# RedBot.net
KiCad netlist of a schematic drawn in EAGLE
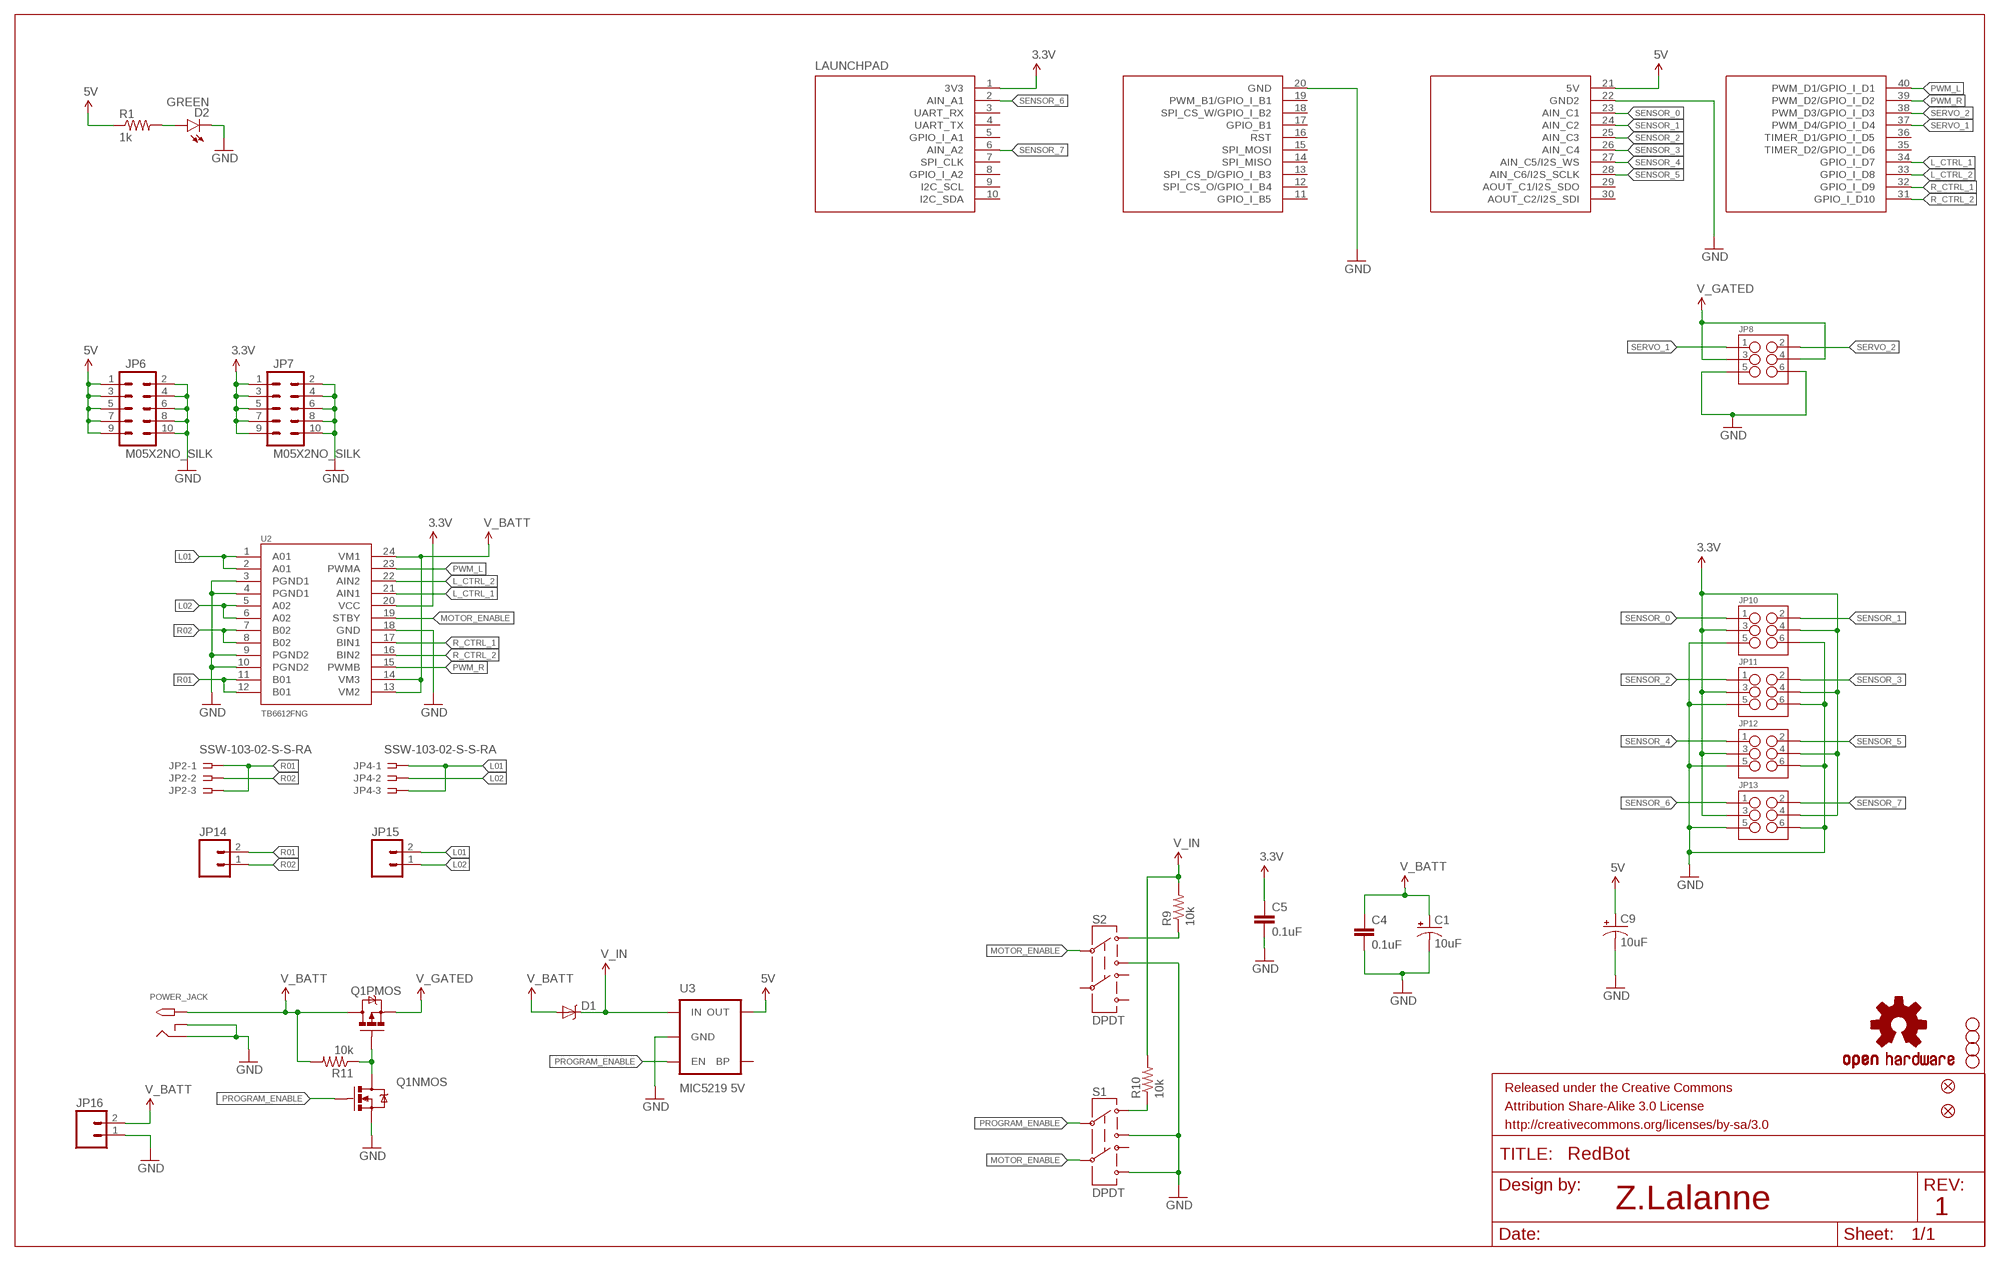
[diagram p0: schematic, sheet 1]

(export (version "E")
  (design (tool "Eeschema 10.0.6"))
  (components
    (comp (ref "C1")
      (value "10uF")
      (footprint "eagle-import:EIA3216")
      (libsource (lib "eagle-import") (part "10UF-16V-10%(TANT)"))
    )
    (comp (ref "C4")
      (value "0.1uF")
      (footprint "eagle-import:1206")
      (libsource (lib "eagle-import") (part "CAP1206"))
    )
    (comp (ref "C5")
      (value "0.1uF")
      (footprint "eagle-import:1206")
      (libsource (lib "eagle-import") (part "CAP1206"))
    )
    (comp (ref "C9")
      (value "10uF")
      (footprint "eagle-import:EIA3216")
      (libsource (lib "eagle-import") (part "10UF-16V-10%(TANT)"))
    )
    (comp (ref "D1")
      (value "B340A")
      (footprint "eagle-import:SMA-DIODE")
      (libsource (lib "eagle-import") (part "B340A"))
    )
    (comp (ref "D2")
      (value "GREEN")
      (footprint "eagle-import:LED-1206")
      (libsource (lib "eagle-import") (part "LED-GREENLARGE"))
    )
    (comp (ref "FID1")
      (value "FIDUCIALUFIDUCIAL")
      (footprint "eagle-import:MICRO-FIDUCIAL")
      (libsource (lib "eagle-import") (part "FIDUCIALUFIDUCIAL"))
    )
    (comp (ref "FID2")
      (value "FIDUCIALUFIDUCIAL")
      (footprint "eagle-import:MICRO-FIDUCIAL")
      (libsource (lib "eagle-import") (part "FIDUCIALUFIDUCIAL"))
    )
    (comp (ref "FRAME1")
      (value "FRAME-LETTER")
      (footprint "eagle-import:CREATIVE_COMMONS")
      (libsource (lib "eagle-import") (part "FRAME-LETTER"))
    )
    (comp (ref "JP2")
      (value "SSW-103-02-S-S-RA")
      (footprint "eagle-import:SSW-103-02-S-S-RA")
      (libsource (lib "eagle-import") (part "SSW-103-02-S-S-RA"))
    )
    (comp (ref "JP4")
      (value "SSW-103-02-S-S-RA")
      (footprint "eagle-import:SSW-103-02-S-S-RA")
      (libsource (lib "eagle-import") (part "SSW-103-02-S-S-RA"))
    )
    (comp (ref "JP6")
      (value "M05X2NO_SILK")
      (footprint "eagle-import:2X5_NOSILK")
      (libsource (lib "eagle-import") (part "M05X2NO_SILK"))
    )
    (comp (ref "JP7")
      (value "M05X2NO_SILK")
      (footprint "eagle-import:2X5_NOSILK")
      (libsource (lib "eagle-import") (part "M05X2NO_SILK"))
    )
    (comp (ref "JP8")
      (value "M03X22X3_SILK_SM")
      (footprint "eagle-import:2X3")
      (libsource (lib "eagle-import") (part "M03X22X3_SILK_SM"))
    )
    (comp (ref "JP10")
      (value "M03X22X3_SILK_SM")
      (footprint "eagle-import:2X3")
      (libsource (lib "eagle-import") (part "M03X22X3_SILK_SM"))
    )
    (comp (ref "JP11")
      (value "M03X22X3_SILK_SM")
      (footprint "eagle-import:2X3")
      (libsource (lib "eagle-import") (part "M03X22X3_SILK_SM"))
    )
    (comp (ref "JP12")
      (value "M03X22X3_SILK_SM")
      (footprint "eagle-import:2X3")
      (libsource (lib "eagle-import") (part "M03X22X3_SILK_SM"))
    )
    (comp (ref "JP13")
      (value "M03X22X3_SILK_SM")
      (footprint "eagle-import:2X3")
      (libsource (lib "eagle-import") (part "M03X22X3_SILK_SM"))
    )
    (comp (ref "JP14")
      (value "M02PTH")
      (footprint "eagle-import:1X02")
      (libsource (lib "eagle-import") (part "M02PTH"))
    )
    (comp (ref "JP15")
      (value "M02PTH")
      (footprint "eagle-import:1X02")
      (libsource (lib "eagle-import") (part "M02PTH"))
    )
    (comp (ref "JP16")
      (value "M02PTH")
      (footprint "eagle-import:1X02")
      (libsource (lib "eagle-import") (part "M02PTH"))
    )
    (comp (ref "LAUNCHPAD")
      (value "BOOSTERPACK")
      (footprint "eagle-import:BOOSTERPACK40")
      (libsource (lib "eagle-import") (part "BOOSTERPACK"))
    )
    (comp (ref "POWER_JACK")
      (value "2.1MMJACKTHM")
      (footprint "eagle-import:PJ-102A")
      (libsource (lib "eagle-import") (part "2.1MMJACKTHM"))
    )
    (comp (ref "Q1")
      (value "IRF7509")
      (footprint "eagle-import:MSOP8")
      (libsource (lib "eagle-import") (part "IRF7509"))
    )
    (comp (ref "R1")
      (value "1k")
      (footprint "eagle-import:1206")
      (libsource (lib "eagle-import") (part "RESISTOR1206"))
    )
    (comp (ref "R9")
      (value "10k")
      (footprint "eagle-import:1206")
      (libsource (lib "eagle-import") (part "RESISTOR1206"))
    )
    (comp (ref "R10")
      (value "10k")
      (footprint "eagle-import:1206")
      (libsource (lib "eagle-import") (part "RESISTOR1206"))
    )
    (comp (ref "R11")
      (value "10k")
      (footprint "eagle-import:1206")
      (libsource (lib "eagle-import") (part "RESISTOR1206"))
    )
    (comp (ref "S1")
      (value "DPDT")
      (footprint "eagle-import:AYZ0202")
      (libsource (lib "eagle-import") (part "SWITCH-DPDTAYZ0202"))
    )
    (comp (ref "S2")
      (value "DPDT")
      (footprint "eagle-import:AYZ0202")
      (libsource (lib "eagle-import") (part "SWITCH-DPDTAYZ0202"))
    )
    (comp (ref "STANDOFF1")
      (value "STAND-OFF")
      (footprint "eagle-import:STAND-OFF")
      (libsource (lib "eagle-import") (part "STAND-OFF"))
    )
    (comp (ref "STANDOFF2")
      (value "STAND-OFF")
      (footprint "eagle-import:STAND-OFF")
      (libsource (lib "eagle-import") (part "STAND-OFF"))
    )
    (comp (ref "STANDOFF3")
      (value "STAND-OFF")
      (footprint "eagle-import:STAND-OFF")
      (libsource (lib "eagle-import") (part "STAND-OFF"))
    )
    (comp (ref "STANDOFF4")
      (value "STAND-OFF")
      (footprint "eagle-import:STAND-OFF")
      (libsource (lib "eagle-import") (part "STAND-OFF"))
    )
    (comp (ref "U$17")
      (value "OSHW-LOGOS")
      (footprint "eagle-import:OSHW-LOGO-S")
      (libsource (lib "eagle-import") (part "OSHW-LOGOS"))
    )
    (comp (ref "U2")
      (value "TB6612FNG")
      (footprint "eagle-import:SSOP24")
      (libsource (lib "eagle-import") (part "TB6621FNG"))
    )
    (comp (ref "U3")
      (value "MIC5219 5V")
      (footprint "eagle-import:SOT23-5")
      (fields (field (name "PROD_ID") "VREG-10107"))
      (libsource (lib "eagle-import") (part "V_REG_MIC52195V"))
    )
  )
  (nets
    (net (code "1") (name "3.3V") (class "Default")
      (node (ref "C5") (pin "1") (pinfunction "1_1") (pintype "passive"))
      (node (ref "JP10") (pin "3") (pinfunction "3_3") (pintype "bidirectional"))
      (node (ref "JP10") (pin "4") (pinfunction "4_4") (pintype "bidirectional"))
      (node (ref "JP11") (pin "3") (pinfunction "3_3") (pintype "bidirectional"))
      (node (ref "JP11") (pin "4") (pinfunction "4_4") (pintype "bidirectional"))
      (node (ref "JP12") (pin "3") (pinfunction "3_3") (pintype "bidirectional"))
      (node (ref "JP12") (pin "4") (pinfunction "4_4") (pintype "bidirectional"))
      (node (ref "JP13") (pin "3") (pinfunction "3_3") (pintype "bidirectional"))
      (node (ref "JP13") (pin "4") (pinfunction "4_4") (pintype "bidirectional"))
      (node (ref "JP7") (pin "1") (pinfunction "1_1") (pintype "passive"))
      (node (ref "JP7") (pin "3") (pinfunction "3_3") (pintype "passive"))
      (node (ref "JP7") (pin "5") (pinfunction "5_5") (pintype "passive"))
      (node (ref "JP7") (pin "7") (pinfunction "7_7") (pintype "passive"))
      (node (ref "JP7") (pin "9") (pinfunction "9_9") (pintype "passive"))
      (node (ref "LAUNCHPAD") (pin "1") (pinfunction "3V3_1") (pintype "power_in"))
      (node (ref "U2") (pin "20") (pinfunction "VCC_20") (pintype "bidirectional"))
    )
    (net (code "2") (name "5V") (class "Default")
      (node (ref "C9") (pin "A") (pinfunction "+_A") (pintype "passive"))
      (node (ref "JP6") (pin "1") (pinfunction "1_1") (pintype "passive"))
      (node (ref "JP6") (pin "3") (pinfunction "3_3") (pintype "passive"))
      (node (ref "JP6") (pin "5") (pinfunction "5_5") (pintype "passive"))
      (node (ref "JP6") (pin "7") (pinfunction "7_7") (pintype "passive"))
      (node (ref "JP6") (pin "9") (pinfunction "9_9") (pintype "passive"))
      (node (ref "LAUNCHPAD") (pin "21") (pinfunction "5V_21") (pintype "power_in"))
      (node (ref "R1") (pin "1") (pinfunction "1_1") (pintype "passive"))
      (node (ref "U3") (pin "5") (pinfunction "OUT_5") (pintype "passive"))
    )
    (net (code "3") (name "GND") (class "Default")
      (node (ref "C1") (pin "C") (pinfunction "-_C") (pintype "passive"))
      (node (ref "C4") (pin "2") (pinfunction "2_2") (pintype "passive"))
      (node (ref "C5") (pin "2") (pinfunction "2_2") (pintype "passive"))
      (node (ref "C9") (pin "C") (pinfunction "-_C") (pintype "passive"))
      (node (ref "D2") (pin "C") (pinfunction "C_C") (pintype "passive"))
      (node (ref "JP10") (pin "5") (pinfunction "5_5") (pintype "bidirectional"))
      (node (ref "JP10") (pin "6") (pinfunction "6_6") (pintype "bidirectional"))
      (node (ref "JP11") (pin "5") (pinfunction "5_5") (pintype "bidirectional"))
      (node (ref "JP11") (pin "6") (pinfunction "6_6") (pintype "bidirectional"))
      (node (ref "JP12") (pin "5") (pinfunction "5_5") (pintype "bidirectional"))
      (node (ref "JP12") (pin "6") (pinfunction "6_6") (pintype "bidirectional"))
      (node (ref "JP13") (pin "5") (pinfunction "5_5") (pintype "bidirectional"))
      (node (ref "JP13") (pin "6") (pinfunction "6_6") (pintype "bidirectional"))
      (node (ref "JP16") (pin "1") (pinfunction "1_1") (pintype "passive"))
      (node (ref "JP6") (pin "10") (pinfunction "10_10") (pintype "passive"))
      (node (ref "JP6") (pin "2") (pinfunction "2_2") (pintype "passive"))
      (node (ref "JP6") (pin "4") (pinfunction "4_4") (pintype "passive"))
      (node (ref "JP6") (pin "6") (pinfunction "6_6") (pintype "passive"))
      (node (ref "JP6") (pin "8") (pinfunction "8_8") (pintype "passive"))
      (node (ref "JP7") (pin "10") (pinfunction "10_10") (pintype "passive"))
      (node (ref "JP7") (pin "2") (pinfunction "2_2") (pintype "passive"))
      (node (ref "JP7") (pin "4") (pinfunction "4_4") (pintype "passive"))
      (node (ref "JP7") (pin "6") (pinfunction "6_6") (pintype "passive"))
      (node (ref "JP7") (pin "8") (pinfunction "8_8") (pintype "passive"))
      (node (ref "JP8") (pin "5") (pinfunction "5_5") (pintype "bidirectional"))
      (node (ref "JP8") (pin "6") (pinfunction "6_6") (pintype "bidirectional"))
      (node (ref "LAUNCHPAD") (pin "20") (pinfunction "GND_20") (pintype "power_in"))
      (node (ref "LAUNCHPAD") (pin "22") (pinfunction "GND2_22") (pintype "power_in"))
      (node (ref "POWER_JACK") (pin "RING") (pinfunction "RING_RING") (pintype "bidirectional"))
      (node (ref "POWER_JACK") (pin "RING_SW") (pinfunction "RING_SW_RING_SW") (pintype "bidirectional"))
      (node (ref "Q1") (pin "1") (pinfunction "S_1") (pintype "passive"))
      (node (ref "S1") (pin "3") (pinfunction "3_3") (pintype "bidirectional"))
      (node (ref "S1") (pin "6") (pinfunction "6_6") (pintype "bidirectional"))
      (node (ref "S2") (pin "3") (pinfunction "3_3") (pintype "bidirectional"))
      (node (ref "U2") (pin "10") (pinfunction "PGND2_10") (pintype "bidirectional"))
      (node (ref "U2") (pin "18") (pinfunction "GND_18") (pintype "bidirectional"))
      (node (ref "U2") (pin "3") (pinfunction "PGND1_3") (pintype "bidirectional"))
      (node (ref "U2") (pin "4") (pinfunction "PGND1_4") (pintype "bidirectional"))
      (node (ref "U2") (pin "9") (pinfunction "PGND2_9") (pintype "bidirectional"))
      (node (ref "U3") (pin "2") (pinfunction "GND_2") (pintype "input"))
    )
    (net (code "4") (name "L01") (class "Default")
      (node (ref "JP15") (pin "2") (pinfunction "2_2") (pintype "passive"))
      (node (ref "JP4") (pin "1") (pinfunction "1_1") (pintype "passive"))
      (node (ref "JP4") (pin "3") (pinfunction "1_3") (pintype "passive"))
      (node (ref "U2") (pin "1") (pinfunction "A01_1") (pintype "bidirectional"))
      (node (ref "U2") (pin "2") (pinfunction "A01_2") (pintype "bidirectional"))
    )
    (net (code "5") (name "L02") (class "Default")
      (node (ref "JP15") (pin "1") (pinfunction "1_1") (pintype "passive"))
      (node (ref "JP4") (pin "2") (pinfunction "1_2") (pintype "passive"))
      (node (ref "U2") (pin "5") (pinfunction "A02_5") (pintype "bidirectional"))
      (node (ref "U2") (pin "6") (pinfunction "A02_6") (pintype "bidirectional"))
    )
    (net (code "6") (name "L_CTRL_1") (class "Default")
      (node (ref "LAUNCHPAD") (pin "34") (pinfunction "GPIO_I_D7_34") (pintype "bidirectional"))
      (node (ref "U2") (pin "21") (pinfunction "AIN1_21") (pintype "bidirectional"))
    )
    (net (code "7") (name "L_CTRL_2") (class "Default")
      (node (ref "LAUNCHPAD") (pin "33") (pinfunction "GPIO_I_D8_33") (pintype "bidirectional"))
      (node (ref "U2") (pin "22") (pinfunction "AIN2_22") (pintype "bidirectional"))
    )
    (net (code "8") (name "MOTOR_ENABLE") (class "Default")
      (node (ref "S1") (pin "5") (pinfunction "5_5") (pintype "bidirectional"))
      (node (ref "S2") (pin "2") (pinfunction "2_2") (pintype "bidirectional"))
      (node (ref "U2") (pin "19") (pinfunction "STBY_19") (pintype "bidirectional"))
    )
    (net (code "9") (name "Net-(D2-PadA)") (class "Default")
      (node (ref "D2") (pin "A") (pinfunction "A_A") (pintype "passive"))
      (node (ref "R1") (pin "2") (pinfunction "2_2") (pintype "passive"))
    )
    (net (code "10") (name "Net-(Q1B-G)") (class "Default")
      (node (ref "Q1") (pin "4") (pinfunction "G_4") (pintype "passive"))
      (node (ref "Q1") (pin "7") (pinfunction "D_7") (pintype "passive"))
      (node (ref "Q1") (pin "8") (pinfunction "D_8") (pintype "passive"))
      (node (ref "R11") (pin "1") (pinfunction "1_1") (pintype "passive"))
    )
    (net (code "11") (name "Net-(R9-Pad1)") (class "Default")
      (node (ref "R9") (pin "1") (pinfunction "1_1") (pintype "passive"))
      (node (ref "S2") (pin "1") (pinfunction "1_1") (pintype "bidirectional"))
    )
    (net (code "12") (name "Net-(R10-Pad1)") (class "Default")
      (node (ref "R10") (pin "1") (pinfunction "1_1") (pintype "passive"))
      (node (ref "S1") (pin "1") (pinfunction "1_1") (pintype "bidirectional"))
    )
    (net (code "13") (name "PROGRAM_ENABLE") (class "Default")
      (node (ref "Q1") (pin "2") (pinfunction "G_2") (pintype "passive"))
      (node (ref "S1") (pin "2") (pinfunction "2_2") (pintype "bidirectional"))
      (node (ref "U3") (pin "3") (pinfunction "EN_3") (pintype "input"))
    )
    (net (code "14") (name "PWM_L") (class "Default")
      (node (ref "LAUNCHPAD") (pin "40") (pinfunction "PWM_D1/GPIO_I_D1_40") (pintype "bidirectional"))
      (node (ref "U2") (pin "23") (pinfunction "PWMA_23") (pintype "bidirectional"))
    )
    (net (code "15") (name "PWM_R") (class "Default")
      (node (ref "LAUNCHPAD") (pin "39") (pinfunction "PWM_D2/GPIO_I_D2_39") (pintype "bidirectional"))
      (node (ref "U2") (pin "15") (pinfunction "PWMB_15") (pintype "bidirectional"))
    )
    (net (code "16") (name "R01") (class "Default")
      (node (ref "JP14") (pin "2") (pinfunction "2_2") (pintype "passive"))
      (node (ref "JP2") (pin "1") (pinfunction "1_1") (pintype "passive"))
      (node (ref "JP2") (pin "3") (pinfunction "1_3") (pintype "passive"))
      (node (ref "U2") (pin "11") (pinfunction "B01_11") (pintype "bidirectional"))
      (node (ref "U2") (pin "12") (pinfunction "B01_12") (pintype "bidirectional"))
    )
    (net (code "17") (name "R02") (class "Default")
      (node (ref "JP14") (pin "1") (pinfunction "1_1") (pintype "passive"))
      (node (ref "JP2") (pin "2") (pinfunction "1_2") (pintype "passive"))
      (node (ref "U2") (pin "7") (pinfunction "B02_7") (pintype "bidirectional"))
      (node (ref "U2") (pin "8") (pinfunction "B02_8") (pintype "bidirectional"))
    )
    (net (code "18") (name "R_CTRL_1") (class "Default")
      (node (ref "LAUNCHPAD") (pin "32") (pinfunction "GPIO_I_D9_32") (pintype "bidirectional"))
      (node (ref "U2") (pin "17") (pinfunction "BIN1_17") (pintype "bidirectional"))
    )
    (net (code "19") (name "R_CTRL_2") (class "Default")
      (node (ref "LAUNCHPAD") (pin "31") (pinfunction "GPIO_I_D10_31") (pintype "bidirectional"))
      (node (ref "U2") (pin "16") (pinfunction "BIN2_16") (pintype "bidirectional"))
    )
    (net (code "20") (name "SENSOR_0") (class "Default")
      (node (ref "JP10") (pin "1") (pinfunction "1_1") (pintype "bidirectional"))
      (node (ref "LAUNCHPAD") (pin "23") (pinfunction "AIN_C1_23") (pintype "bidirectional"))
    )
    (net (code "21") (name "SENSOR_1") (class "Default")
      (node (ref "JP10") (pin "2") (pinfunction "2_2") (pintype "bidirectional"))
      (node (ref "LAUNCHPAD") (pin "24") (pinfunction "AIN_C2_24") (pintype "bidirectional"))
    )
    (net (code "22") (name "SENSOR_2") (class "Default")
      (node (ref "JP11") (pin "1") (pinfunction "1_1") (pintype "bidirectional"))
      (node (ref "LAUNCHPAD") (pin "25") (pinfunction "AIN_C3_25") (pintype "bidirectional"))
    )
    (net (code "23") (name "SENSOR_3") (class "Default")
      (node (ref "JP11") (pin "2") (pinfunction "2_2") (pintype "bidirectional"))
      (node (ref "LAUNCHPAD") (pin "26") (pinfunction "AIN_C4_26") (pintype "bidirectional"))
    )
    (net (code "24") (name "SENSOR_4") (class "Default")
      (node (ref "JP12") (pin "1") (pinfunction "1_1") (pintype "bidirectional"))
      (node (ref "LAUNCHPAD") (pin "27") (pinfunction "AIN_C5/I2S_WS_27") (pintype "bidirectional"))
    )
    (net (code "25") (name "SENSOR_5") (class "Default")
      (node (ref "JP12") (pin "2") (pinfunction "2_2") (pintype "bidirectional"))
      (node (ref "LAUNCHPAD") (pin "28") (pinfunction "AIN_C6/I2S_SCLK_28") (pintype "bidirectional"))
    )
    (net (code "26") (name "SENSOR_6") (class "Default")
      (node (ref "JP13") (pin "1") (pinfunction "1_1") (pintype "bidirectional"))
      (node (ref "LAUNCHPAD") (pin "2") (pinfunction "AIN_A1_2") (pintype "bidirectional"))
    )
    (net (code "27") (name "SENSOR_7") (class "Default")
      (node (ref "JP13") (pin "2") (pinfunction "2_2") (pintype "bidirectional"))
      (node (ref "LAUNCHPAD") (pin "6") (pinfunction "AIN_A2_6") (pintype "bidirectional"))
    )
    (net (code "28") (name "SERVO_1") (class "Default")
      (node (ref "JP8") (pin "1") (pinfunction "1_1") (pintype "bidirectional"))
      (node (ref "LAUNCHPAD") (pin "37") (pinfunction "PWM_D4/GPIO_I_D4_37") (pintype "bidirectional"))
    )
    (net (code "29") (name "SERVO_2") (class "Default")
      (node (ref "JP8") (pin "2") (pinfunction "2_2") (pintype "bidirectional"))
      (node (ref "LAUNCHPAD") (pin "38") (pinfunction "PWM_D3/GPIO_I_D3_38") (pintype "bidirectional"))
    )
    (net (code "30") (name "V_BATT") (class "Default")
      (node (ref "C1") (pin "A") (pinfunction "+_A") (pintype "passive"))
      (node (ref "C4") (pin "1") (pinfunction "1_1") (pintype "passive"))
      (node (ref "D1") (pin "A") (pinfunction "A_A") (pintype "passive"))
      (node (ref "JP16") (pin "2") (pinfunction "2_2") (pintype "passive"))
      (node (ref "POWER_JACK") (pin "TIP") (pinfunction "TIP_TIP") (pintype "bidirectional"))
      (node (ref "Q1") (pin "5") (pinfunction "D_5") (pintype "passive"))
      (node (ref "Q1") (pin "6") (pinfunction "D_6") (pintype "passive"))
      (node (ref "R11") (pin "2") (pinfunction "2_2") (pintype "passive"))
      (node (ref "U2") (pin "13") (pinfunction "VM2_13") (pintype "bidirectional"))
      (node (ref "U2") (pin "14") (pinfunction "VM3_14") (pintype "bidirectional"))
      (node (ref "U2") (pin "24") (pinfunction "VM1_24") (pintype "bidirectional"))
    )
    (net (code "31") (name "V_GATED") (class "Default")
      (node (ref "JP8") (pin "3") (pinfunction "3_3") (pintype "bidirectional"))
      (node (ref "JP8") (pin "4") (pinfunction "4_4") (pintype "bidirectional"))
      (node (ref "Q1") (pin "3") (pinfunction "S_3") (pintype "passive"))
    )
    (net (code "32") (name "V_IN") (class "Default")
      (node (ref "D1") (pin "C") (pinfunction "C_C") (pintype "passive"))
      (node (ref "R10") (pin "2") (pinfunction "2_2") (pintype "passive"))
      (node (ref "R9") (pin "2") (pinfunction "2_2") (pintype "passive"))
      (node (ref "U3") (pin "1") (pinfunction "IN_1") (pintype "input"))
    )
    (net (code "33") (name "unconnected-(LAUNCHPAD-AOUT_C1{slash}I2S_SDO-Pad29)") (class "Default")
      (node (ref "LAUNCHPAD") (pin "29") (pinfunction "AOUT_C1/I2S_SDO_29") (pintype "bidirectional"))
    )
    (net (code "34") (name "unconnected-(LAUNCHPAD-AOUT_C2{slash}I2S_SDI-Pad30)") (class "Default")
      (node (ref "LAUNCHPAD") (pin "30") (pinfunction "AOUT_C2/I2S_SDI_30") (pintype "bidirectional"))
    )
    (net (code "35") (name "unconnected-(LAUNCHPAD-GPIO_B1-Pad17)") (class "Default")
      (node (ref "LAUNCHPAD") (pin "17") (pinfunction "GPIO_B1_17") (pintype "bidirectional"))
    )
    (net (code "36") (name "unconnected-(LAUNCHPAD-GPIO_I_A1-Pad5)") (class "Default")
      (node (ref "LAUNCHPAD") (pin "5") (pinfunction "GPIO_I_A1_5") (pintype "bidirectional"))
    )
    (net (code "37") (name "unconnected-(LAUNCHPAD-GPIO_I_A2-Pad8)") (class "Default")
      (node (ref "LAUNCHPAD") (pin "8") (pinfunction "GPIO_I_A2_8") (pintype "bidirectional"))
    )
    (net (code "38") (name "unconnected-(LAUNCHPAD-GPIO_I_B5-Pad11)") (class "Default")
      (node (ref "LAUNCHPAD") (pin "11") (pinfunction "GPIO_I_B5_11") (pintype "bidirectional"))
    )
    (net (code "39") (name "unconnected-(LAUNCHPAD-I2C_SCL-Pad9)") (class "Default")
      (node (ref "LAUNCHPAD") (pin "9") (pinfunction "I2C_SCL_9") (pintype "bidirectional"))
    )
    (net (code "40") (name "unconnected-(LAUNCHPAD-I2C_SDA-Pad10)") (class "Default")
      (node (ref "LAUNCHPAD") (pin "10") (pinfunction "I2C_SDA_10") (pintype "bidirectional"))
    )
    (net (code "41") (name "unconnected-(LAUNCHPAD-PWM_B1{slash}GPIO_I_B1-Pad19)") (class "Default")
      (node (ref "LAUNCHPAD") (pin "19") (pinfunction "PWM_B1/GPIO_I_B1_19") (pintype "bidirectional"))
    )
    (net (code "42") (name "unconnected-(LAUNCHPAD-RST-Pad16)") (class "Default")
      (node (ref "LAUNCHPAD") (pin "16") (pinfunction "RST_16") (pintype "bidirectional"))
    )
    (net (code "43") (name "unconnected-(LAUNCHPAD-SPI_CLK-Pad7)") (class "Default")
      (node (ref "LAUNCHPAD") (pin "7") (pinfunction "SPI_CLK_7") (pintype "bidirectional"))
    )
    (net (code "44") (name "unconnected-(LAUNCHPAD-SPI_CS_D{slash}GPIO_I_B3-Pad13)") (class "Default")
      (node (ref "LAUNCHPAD") (pin "13") (pinfunction "SPI_CS_D/GPIO_I_B3_13") (pintype "bidirectional"))
    )
    (net (code "45") (name "unconnected-(LAUNCHPAD-SPI_CS_O{slash}GPIO_I_B4-Pad12)") (class "Default")
      (node (ref "LAUNCHPAD") (pin "12") (pinfunction "SPI_CS_O/GPIO_I_B4_12") (pintype "bidirectional"))
    )
    (net (code "46") (name "unconnected-(LAUNCHPAD-SPI_CS_W{slash}GPIO_I_B2-Pad18)") (class "Default")
      (node (ref "LAUNCHPAD") (pin "18") (pinfunction "SPI_CS_W/GPIO_I_B2_18") (pintype "bidirectional"))
    )
    (net (code "47") (name "unconnected-(LAUNCHPAD-SPI_MISO-Pad14)") (class "Default")
      (node (ref "LAUNCHPAD") (pin "14") (pinfunction "SPI_MISO_14") (pintype "bidirectional"))
    )
    (net (code "48") (name "unconnected-(LAUNCHPAD-SPI_MOSI-Pad15)") (class "Default")
      (node (ref "LAUNCHPAD") (pin "15") (pinfunction "SPI_MOSI_15") (pintype "bidirectional"))
    )
    (net (code "49") (name "unconnected-(LAUNCHPAD-TIMER_D1{slash}GPIO_I_D5-Pad36)") (class "Default")
      (node (ref "LAUNCHPAD") (pin "36") (pinfunction "TIMER_D1/GPIO_I_D5_36") (pintype "bidirectional"))
    )
    (net (code "50") (name "unconnected-(LAUNCHPAD-TIMER_D2{slash}GPIO_I_D6-Pad35)") (class "Default")
      (node (ref "LAUNCHPAD") (pin "35") (pinfunction "TIMER_D2/GPIO_I_D6_35") (pintype "bidirectional"))
    )
    (net (code "51") (name "unconnected-(LAUNCHPAD-UART_RX-Pad3)") (class "Default")
      (node (ref "LAUNCHPAD") (pin "3") (pinfunction "UART_RX_3") (pintype "bidirectional"))
    )
    (net (code "52") (name "unconnected-(LAUNCHPAD-UART_TX-Pad4)") (class "Default")
      (node (ref "LAUNCHPAD") (pin "4") (pinfunction "UART_TX_4") (pintype "bidirectional"))
    )
    (net (code "53") (name "unconnected-(S1-Pad4)") (class "Default")
      (node (ref "S1") (pin "4") (pinfunction "4_4") (pintype "bidirectional"))
    )
    (net (code "54") (name "unconnected-(S2-Pad4)") (class "Default")
      (node (ref "S2") (pin "4") (pinfunction "4_4") (pintype "bidirectional"))
    )
    (net (code "55") (name "unconnected-(S2-Pad5)") (class "Default")
      (node (ref "S2") (pin "5") (pinfunction "5_5") (pintype "bidirectional"))
    )
    (net (code "56") (name "unconnected-(S2-Pad6)") (class "Default")
      (node (ref "S2") (pin "6") (pinfunction "6_6") (pintype "bidirectional"))
    )
    (net (code "57") (name "unconnected-(U3-BP-Pad4)") (class "Default")
      (node (ref "U3") (pin "4") (pinfunction "BP_4") (pintype "input"))
    )
  )
)
